# SOT-23-6_to_breadboard.net
KiCad netlist of a schematic drawn in EAGLE
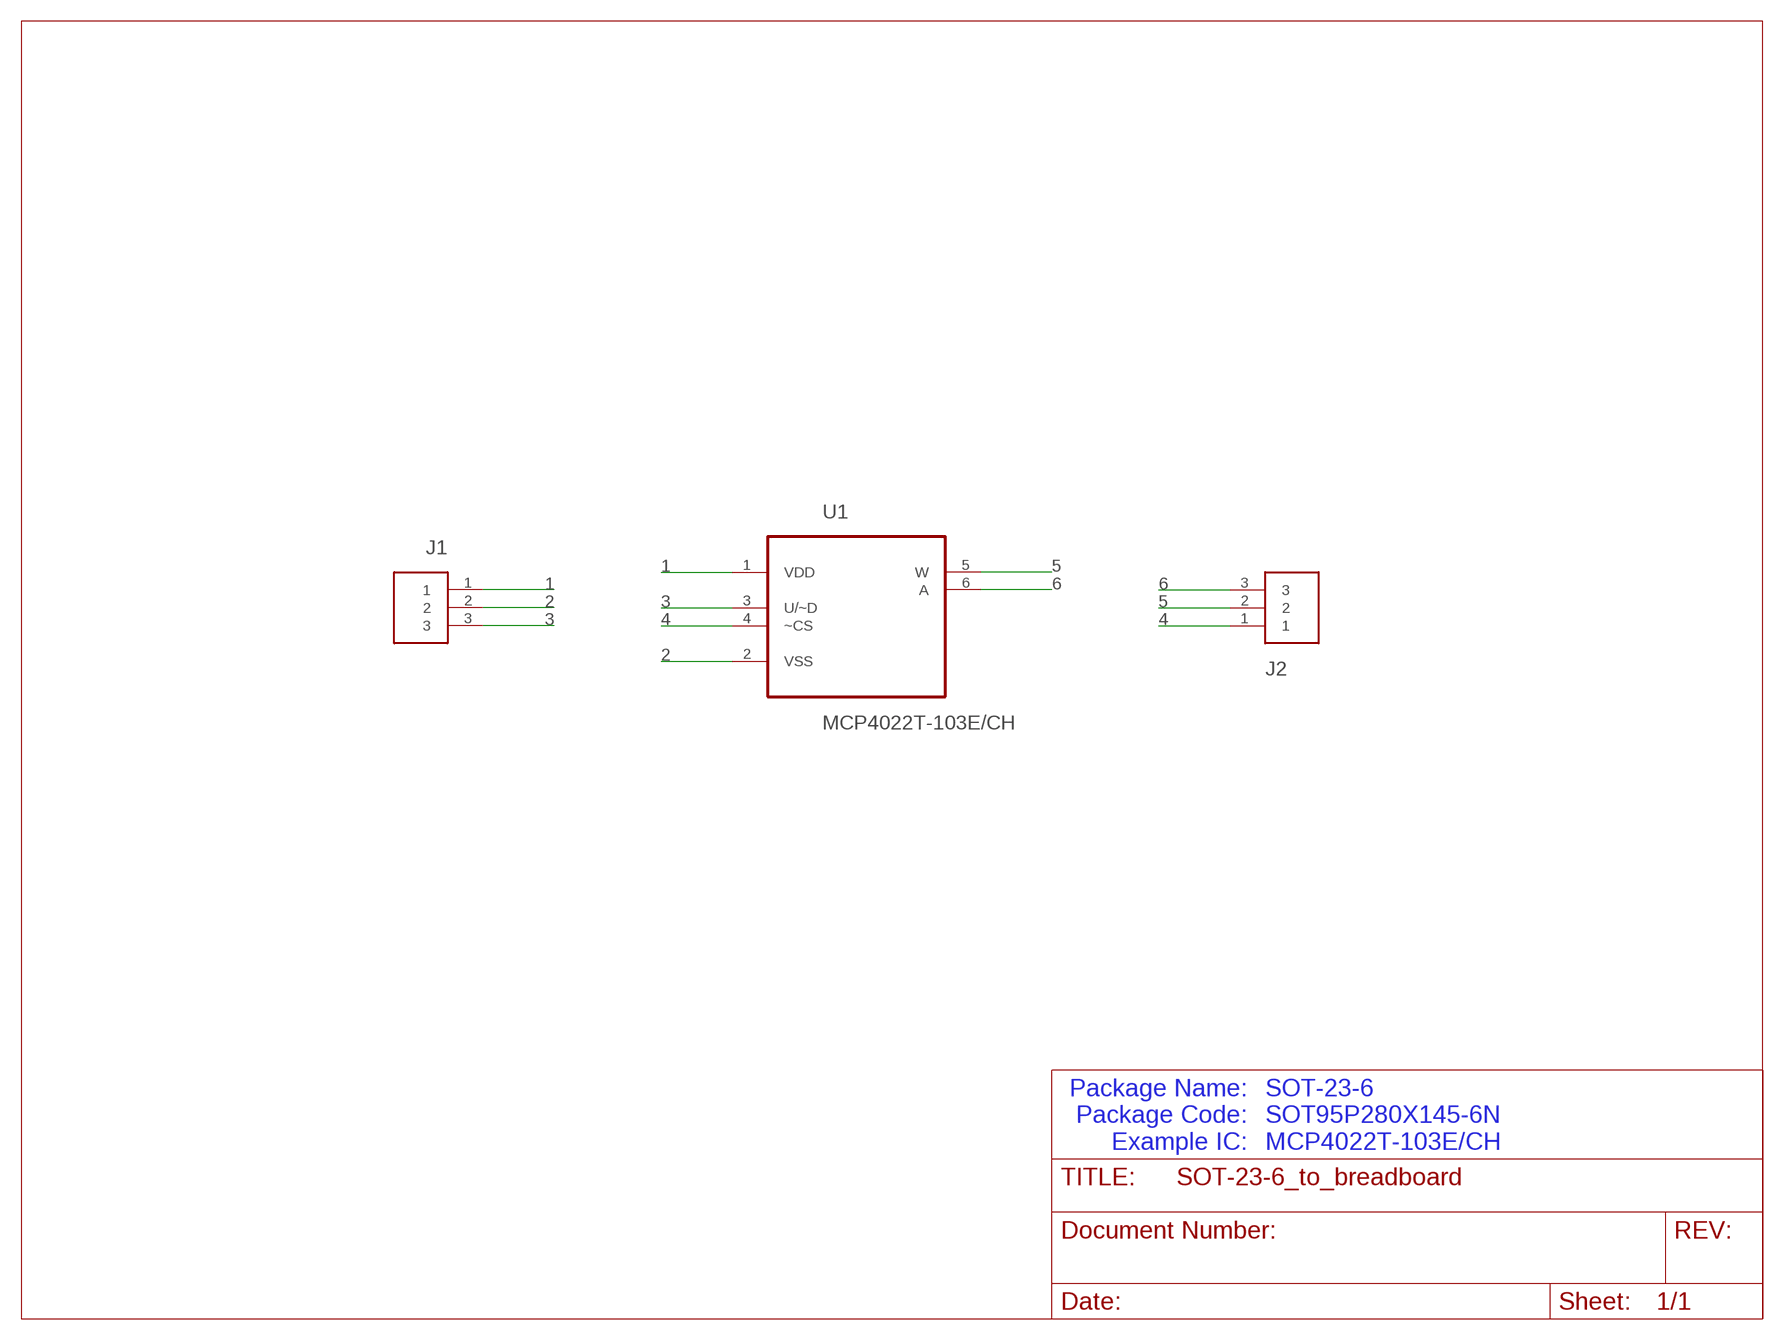
[diagram p0: schematic, sheet 1]

(export (version "E")
  (design (tool "Eeschema 10.0.6"))
  (components
    (comp (ref "J1")
      (value "CONNECTOR_3")
      (footprint "eagle-import:68000-103HLF")
      (libsource (lib "eagle-import") (part "CONNECTOR_3"))
    )
    (comp (ref "J2")
      (value "CONNECTOR_3-NO_SQUARE")
      (footprint "eagle-import:68000-103HLF_NO_SQUARE")
      (libsource (lib "eagle-import") (part "CONNECTOR_3-NO_SQUARE"))
    )
    (comp (ref "U1")
      (value "MCP4022T-103E/CH")
      (footprint "eagle-import:SOT95P280X145-6N")
      (fields (field (name "MF") "Microchip"))
      (libsource (lib "eagle-import") (part "MCP4022T-103E/CH"))
    )
  )
  (nets
    (net (code "1") (name "/1") (class "Default")
      (node (ref "J1") (pin "1") (pinfunction "1_1") (pintype "bidirectional"))
      (node (ref "U1") (pin "1") (pinfunction "VDD_1") (pintype "power_in"))
    )
    (net (code "2") (name "/2") (class "Default")
      (node (ref "J1") (pin "2") (pinfunction "2_2") (pintype "bidirectional"))
      (node (ref "U1") (pin "2") (pinfunction "VSS_2") (pintype "power_in"))
    )
    (net (code "3") (name "/3") (class "Default")
      (node (ref "J1") (pin "3") (pinfunction "3_3") (pintype "bidirectional"))
      (node (ref "U1") (pin "3") (pinfunction "U/~{D}_3") (pintype "input"))
    )
    (net (code "4") (name "/4") (class "Default")
      (node (ref "J2") (pin "1") (pinfunction "1_1") (pintype "bidirectional"))
      (node (ref "U1") (pin "4") (pinfunction "~{CS}_4") (pintype "input"))
    )
    (net (code "5") (name "/5") (class "Default")
      (node (ref "J2") (pin "2") (pinfunction "2_2") (pintype "bidirectional"))
      (node (ref "U1") (pin "5") (pinfunction "W_5") (pintype "passive"))
    )
    (net (code "6") (name "/6") (class "Default")
      (node (ref "J2") (pin "3") (pinfunction "3_3") (pintype "bidirectional"))
      (node (ref "U1") (pin "6") (pinfunction "A_6") (pintype "passive"))
    )
  )
)
